# 1_ADSTM32_Power.net
KiCad netlist of a schematic drawn in Altium Designer
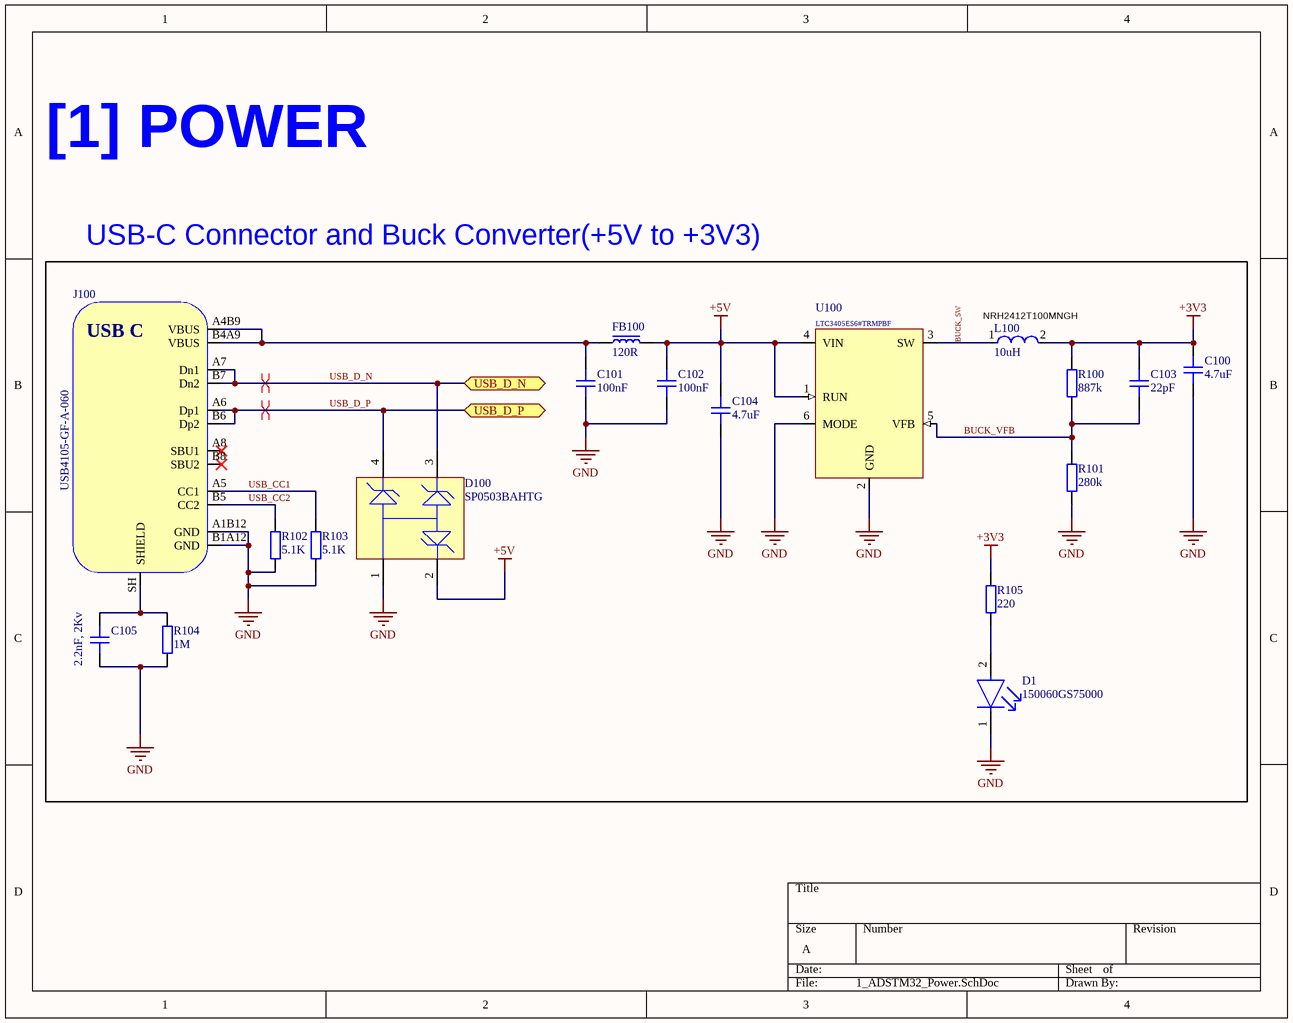
[diagram p0: 1_ADSTM32_Power.SchDoc]

(export (version "E")
  (design (tool "Eeschema 10.0.6"))
  (components
    (comp (ref "C100")
      (value "4.7uF")
      (footprint "CAP_0603")
      (description "Capacitor SMD 0805 16V")
      (libsource (lib "Schematic-Lib-PhilsLab") (part "CAP_0805_16V"))
    )
    (comp (ref "C101")
      (value "100nF")
      (footprint "CAP_0603")
      (description "Capacitor SMD 0603 16V")
      (libsource (lib "Schematic-Lib-PhilsLab") (part "CAP_0603_16V"))
    )
    (comp (ref "C102")
      (value "100nF")
      (footprint "CAP_0603")
      (description "Capacitor SMD 0603 16V")
      (libsource (lib "Schematic-Lib-PhilsLab") (part "CAP_0603_16V"))
    )
    (comp (ref "C103")
      (value "22pF")
      (footprint "CAP_0603")
      (description "Capacitor SMD 0603 16V")
      (libsource (lib "Schematic-Lib-PhilsLab") (part "CAP_0603_16V"))
    )
    (comp (ref "C104")
      (value "4.7uF")
      (footprint "CAP_0603")
      (description "Capacitor SMD 0805 16V")
      (libsource (lib "Schematic-Lib-PhilsLab") (part "CAP_0805_16V"))
    )
    (comp (ref "C105")
      (value "2.2nF, 2Kv")
      (footprint "CAP_0603")
      (description "Capacitor SMD 0805 16V")
      (libsource (lib "Schematic-Lib-PhilsLab") (part "CAP_0805_16V"))
    )
    (comp (ref "D1")
      (value "150060GS75000")
      (footprint "FP-150060GS75000-MFG")
      (description "LED GREEN CLEAR 0603 SMD")
      (libsource (lib "Altium Content Vault") (part "8706943c75ba83719d021d2fdc84c58"))
    )
    (comp (ref "D100")
      (value "SP0503BAHTG")
      (footprint "LFUS-SOT143-4_V")
      (description "TVS Diode Array, 30 pF, 30 KV, -40 to 85 degC, 4-Pin SOT143, RoHS, Tape and Reel")
      (fields (field (name "MANUFACTURER") "Littelfuse"))
      (libsource (lib "Altium Content Vault") (part "LFUS-SP0503BAHTG-SOT143-4"))
    )
    (comp (ref "FB100")
      (value "120R")
      (footprint "FB_0603")
      (description "Ferrite Bead SMD 0603")
      (libsource (lib "Schematic-Lib-PhilsLab") (part "FB_0603"))
    )
    (comp (ref "J100")
      (value "USB4105-GF-A-060")
      (footprint "USB4105-GF-A-060")
      (description "USB Connector Type C SMT 12 Pin")
      (fields (field (name "MANUFACTURER") "GCT"))
      (libsource (lib "Schematic-Lib-PhilsLab") (part "USB4105-GF-A-060"))
    )
    (comp (ref "L100")
      (value "10uH")
      (footprint "FP-NRH2412-MFG")
      (description "NRH2412T100MNGH -Shielded Wirewound Inductor 10uH 20% 0.51A 0.72Ω SMD")
      (fields (field (name "TOLERANCE") "20%"))
      (libsource (lib "Altium Content Vault") (part "725321dda6339637d4d059423bc1c3c"))
    )
    (comp (ref "R100")
      (value "887k")
      (footprint "RES_0603")
      (description "Resistor SMD 0603")
      (libsource (lib "Schematic-Lib-PhilsLab") (part "RES_0603"))
    )
    (comp (ref "R101")
      (value "280k")
      (footprint "RES_0603")
      (description "Resistor SMD 0603")
      (libsource (lib "Schematic-Lib-PhilsLab") (part "RES_0603"))
    )
    (comp (ref "R102")
      (value "5.1K")
      (footprint "RES_0603")
      (description "Resistor SMD 0603")
      (libsource (lib "Schematic-Lib-PhilsLab") (part "RES_0603"))
    )
    (comp (ref "R103")
      (value "5.1K")
      (footprint "RES_0603")
      (description "Resistor SMD 0603")
      (libsource (lib "Schematic-Lib-PhilsLab") (part "RES_0603"))
    )
    (comp (ref "R104")
      (value "1M")
      (footprint "RES_0603")
      (description "Resistor SMD 0805")
      (libsource (lib "Schematic-Lib-PhilsLab") (part "RES_0805"))
    )
    (comp (ref "R105")
      (value "220")
      (footprint "RES_0603")
      (description "Resistor SMD 0603")
      (libsource (lib "Schematic-Lib-PhilsLab") (part "RES_0603"))
    )
    (comp (ref "U100")
      (value "LTC3405ES6#TRMPBF")
      (footprint "SOT-23-6")
      (description "1.5MHz, 300mA\r\nSynchronous Step-Down\r\nRegulator in ThinSOT")
      (fields (field (name "MANUFACTURER") "Analog Devices"))
      (libsource (lib "Schematic-Lib-PhilsLab") (part "LTC3405ES6#TRMPBF"))
    )
  )
  (nets
    (net (code "1") (name "+3V3") (class "Default")
      (node (ref "C100") (pin "2") (pinfunction "2_2") (pintype "passive"))
      (node (ref "C103") (pin "2") (pinfunction "2_2") (pintype "passive"))
      (node (ref "L100") (pin "2") (pinfunction "2_2") (pintype "passive"))
      (node (ref "R100") (pin "2") (pinfunction "2_2") (pintype "passive"))
      (node (ref "R105") (pin "2") (pinfunction "2_2") (pintype "passive"))
    )
    (net (code "2") (name "+5V") (class "Default")
      (node (ref "C102") (pin "2") (pinfunction "2_2") (pintype "passive"))
      (node (ref "C104") (pin "2") (pinfunction "2_2") (pintype "passive"))
      (node (ref "D100") (pin "2") (pinfunction "2_2") (pintype "passive"))
      (node (ref "FB100") (pin "2") (pinfunction "2_2") (pintype "passive"))
      (node (ref "U100") (pin "1") (pinfunction "RUN_1") (pintype "input"))
      (node (ref "U100") (pin "4") (pinfunction "VIN_4") (pintype "power_in"))
    )
    (net (code "3") (name "/BUCK_SW") (class "Default")
      (node (ref "L100") (pin "1") (pinfunction "1_1") (pintype "passive"))
      (node (ref "U100") (pin "3") (pinfunction "SW_3") (pintype "power_in"))
    )
    (net (code "4") (name "/BUCK_VFB") (class "Default")
      (node (ref "C103") (pin "1") (pinfunction "1_1") (pintype "passive"))
      (node (ref "R100") (pin "1") (pinfunction "1_1") (pintype "passive"))
      (node (ref "R101") (pin "2") (pinfunction "2_2") (pintype "passive"))
      (node (ref "U100") (pin "5") (pinfunction "VFB_5") (pintype "input"))
    )
    (net (code "5") (name "/USB_CC1") (class "Default")
      (node (ref "J100") (pin "A5") (pinfunction "CC1_A5") (pintype "passive"))
      (node (ref "R103") (pin "1") (pinfunction "1_1") (pintype "passive"))
    )
    (net (code "6") (name "/USB_CC2") (class "Default")
      (node (ref "J100") (pin "B5") (pinfunction "CC2_B5") (pintype "passive"))
      (node (ref "R102") (pin "1") (pinfunction "1_1") (pintype "passive"))
    )
    (net (code "7") (name "/USB_D_N") (class "Default")
      (node (ref "D100") (pin "3") (pinfunction "3_3") (pintype "passive"))
      (node (ref "J100") (pin "A7") (pinfunction "Dn1_A7") (pintype "passive"))
      (node (ref "J100") (pin "B7") (pinfunction "Dn2_B7") (pintype "passive"))
    )
    (net (code "8") (name "/USB_D_P") (class "Default")
      (node (ref "D100") (pin "4") (pinfunction "4_4") (pintype "passive"))
      (node (ref "J100") (pin "A6") (pinfunction "Dp1_A6") (pintype "passive"))
      (node (ref "J100") (pin "B6") (pinfunction "Dp2_B6") (pintype "passive"))
    )
    (net (code "9") (name "GND") (class "Default")
      (node (ref "C100") (pin "1") (pinfunction "1_1") (pintype "passive"))
      (node (ref "C101") (pin "1") (pinfunction "1_1") (pintype "passive"))
      (node (ref "C102") (pin "1") (pinfunction "1_1") (pintype "passive"))
      (node (ref "C104") (pin "1") (pinfunction "1_1") (pintype "passive"))
      (node (ref "C105") (pin "2") (pinfunction "2_2") (pintype "passive"))
      (node (ref "D1") (pin "1") (pinfunction "C_1") (pintype "passive"))
      (node (ref "D100") (pin "1") (pinfunction "1_1") (pintype "passive"))
      (node (ref "J100") (pin "A1B12") (pinfunction "GND_A1B12") (pintype "passive"))
      (node (ref "J100") (pin "B1A12") (pinfunction "GND_B1A12") (pintype "passive"))
      (node (ref "R101") (pin "1") (pinfunction "1_1") (pintype "passive"))
      (node (ref "R102") (pin "2") (pinfunction "2_2") (pintype "passive"))
      (node (ref "R103") (pin "2") (pinfunction "2_2") (pintype "passive"))
      (node (ref "R104") (pin "2") (pinfunction "2_2") (pintype "passive"))
      (node (ref "U100") (pin "2") (pinfunction "GND_2") (pintype "power_in"))
      (node (ref "U100") (pin "6") (pinfunction "MODE_6") (pintype "passive"))
    )
    (net (code "10") (name "Net-(C101-Pad2)") (class "Default")
      (node (ref "C101") (pin "2") (pinfunction "2_2") (pintype "passive"))
      (node (ref "FB100") (pin "1") (pinfunction "1_1") (pintype "passive"))
      (node (ref "J100") (pin "A4B9") (pinfunction "VBUS_A4B9") (pintype "passive"))
      (node (ref "J100") (pin "B4A9") (pinfunction "VBUS_B4A9") (pintype "passive"))
    )
    (net (code "11") (name "Net-(D1-A)") (class "Default")
      (node (ref "D1") (pin "2") (pinfunction "A_2") (pintype "passive"))
      (node (ref "R105") (pin "1") (pinfunction "1_1") (pintype "passive"))
    )
    (net (code "12") (name "Net-(J100-SHIELD)") (class "Default")
      (node (ref "C105") (pin "1") (pinfunction "1_1") (pintype "passive"))
      (node (ref "J100") (pin "SH") (pinfunction "SHIELD_SH") (pintype "passive"))
      (node (ref "R104") (pin "1") (pinfunction "1_1") (pintype "passive"))
    )
    (net (code "13") (name "unconnected-(J100-SBU1-PadA8)") (class "Default")
      (node (ref "J100") (pin "A8") (pinfunction "SBU1_A8") (pintype "passive+no_connect"))
    )
    (net (code "14") (name "unconnected-(J100-SBU2-PadB8)") (class "Default")
      (node (ref "J100") (pin "B8") (pinfunction "SBU2_B8") (pintype "passive+no_connect"))
    )
  )
)
